# ESP32.net
KiCad netlist of a schematic drawn in Altium Designer
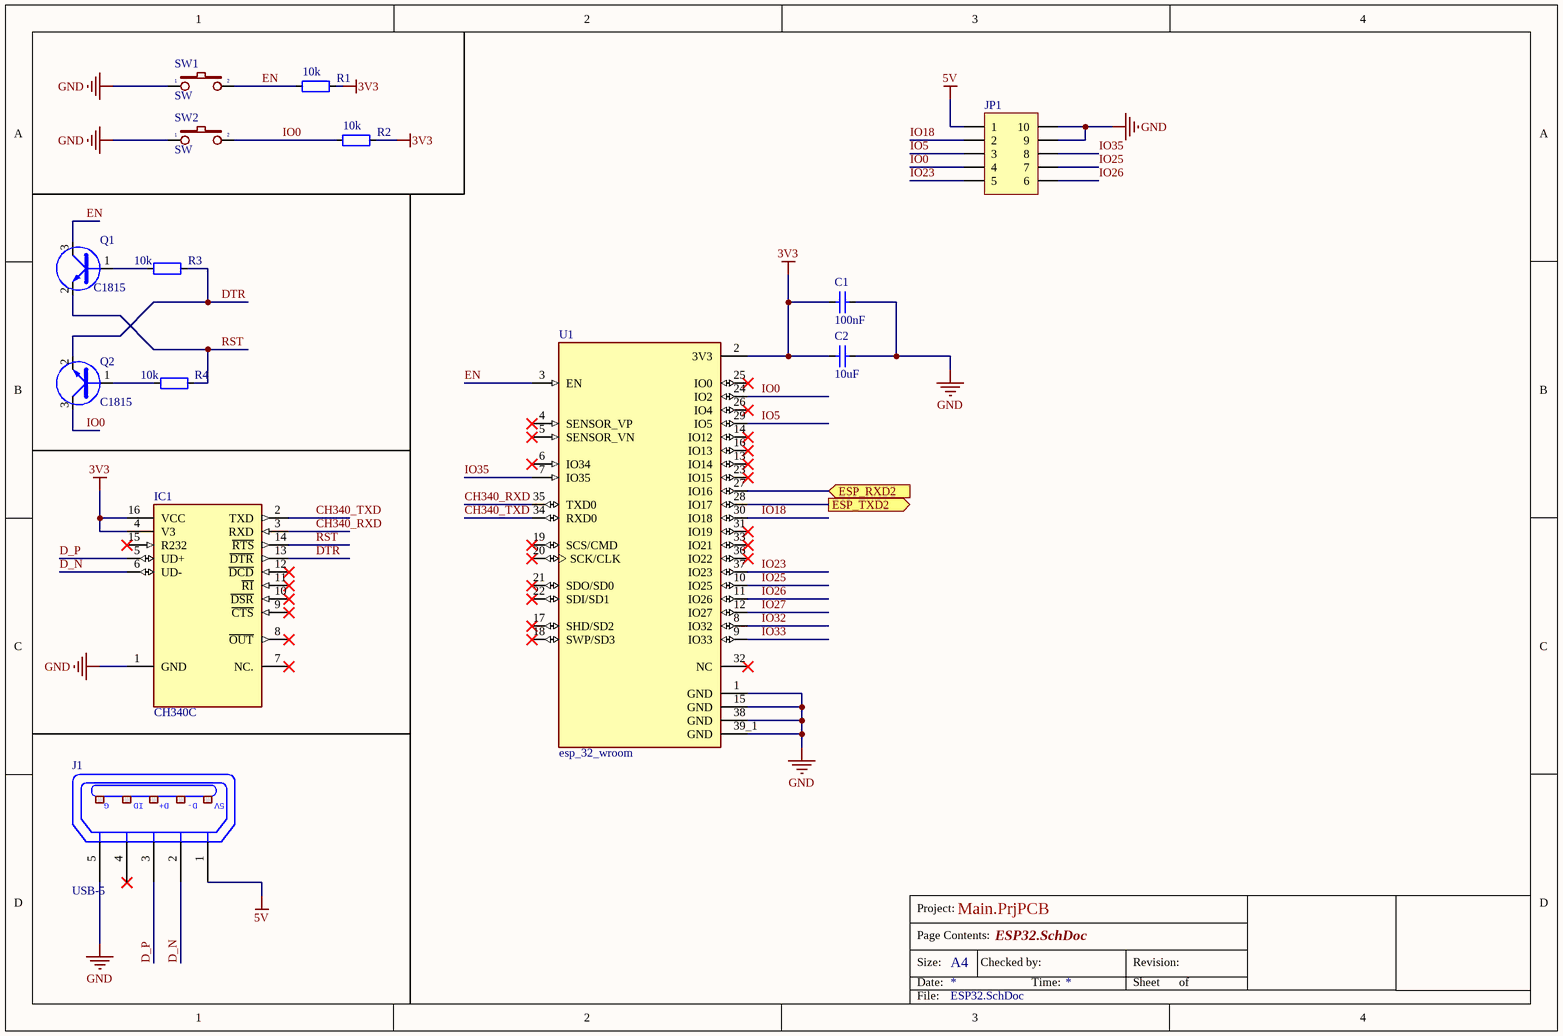
[diagram p0: ESP32.SchDoc]

(export (version "E")
  (design (tool "Eeschema 10.0.6"))
  (components
    (comp (ref "C1")
      (value "100nF")
      (footprint "CAP_0805")
      (description "Capacitor")
      (fields (field (name "PUBLISHER") "Altium Limited"))
      (libsource (lib "My Library") (part "CapSMD"))
    )
    (comp (ref "C2")
      (value "10uF")
      (footprint "CAP_0805")
      (description "Capacitor")
      (fields (field (name "PUBLISHER") "Altium Limited"))
      (libsource (lib "My Library") (part "CapSMD"))
    )
    (comp (ref "IC1") (value "CH340C") (footprint "SO16") (libsource (lib "My Library") (part "CH340C")))
    (comp (ref "J1")
      (value "USB-5")
      (footprint "USB-M1")
      (fields
        (field (name "MANUFACTURER") "FCI")
        (field (name "MANUFACTURER PART NUMBER") "10118193-0001LF")
        (field (name ".CREATOR") "MM")
        (field (name ".CHECKED PCB") "RF")
        (field (name ".CHECKED SCH") "MM")
      )
      (libsource (lib "My Library") (part "USB-5"))
    )
    (comp (ref "JP1")
      (value "JP 2x5 2.54")
      (footprint "JP5-D2T")
      (description "Cắm")
      (libsource (lib "Altium_Lib_by_KhueNguyenCreator") (part "JP 2x5 2.54 Duc Thang"))
    )
    (comp (ref "Q1")
      (value "C1815")
      (footprint "SOT23D")
      (description "NPN 600mW, ECB")
      (libsource (lib "My Library") (part "2SC1815"))
    )
    (comp (ref "Q2")
      (value "C1815")
      (footprint "SOT23D")
      (description "NPN 600mW, ECB")
      (libsource (lib "") (part "2SC1815_1"))
    )
    (comp (ref "R1")
      (value "10k")
      (footprint "RES-SMD-0805")
      (description "Resistor")
      (fields
        (field (name "MANUFACTURER") "Generic Components")
        (field (name "PUBLISHER") "Altium Hobart Technology Centre")
      )
      (libsource (lib "My Library") (part "Resistor - SMD"))
    )
    (comp (ref "R2")
      (value "10k")
      (footprint "RES-SMD-0805")
      (description "Resistor")
      (fields
        (field (name "MANUFACTURER") "Generic Components")
        (field (name "PUBLISHER") "Altium Hobart Technology Centre")
      )
      (libsource (lib "My Library") (part "Resistor - SMD"))
    )
    (comp (ref "R3")
      (value "10k")
      (footprint "RES-SMD-0805")
      (description "Resistor")
      (fields
        (field (name "MANUFACTURER") "Generic Components")
        (field (name "PUBLISHER") "Altium Hobart Technology Centre")
      )
      (libsource (lib "My Library") (part "Resistor - SMD"))
    )
    (comp (ref "R4")
      (value "10k")
      (footprint "RES-SMD-0805")
      (description "Resistor")
      (fields
        (field (name "MANUFACTURER") "Generic Components")
        (field (name "PUBLISHER") "Altium Hobart Technology Centre")
      )
      (libsource (lib "My Library") (part "Resistor - SMD"))
    )
    (comp (ref "SW1")
      (value "SW")
      (footprint "SW2")
      (description "Switch button 2 pin")
      (libsource (lib "My Library") (part "SW2"))
    )
    (comp (ref "SW2")
      (value "SW")
      (footprint "SW2")
      (description "Switch button 2 pin")
      (libsource (lib "My Library") (part "SW2"))
    )
    (comp (ref "U1")
      (value "esp_32_wroom")
      (footprint "MODULE_ESP32-WROOM-32")
      (libsource (lib "My Library") (part "esp_32_wroom"))
    )
  )
  (nets
    (net (code "1") (name "/CH340_RXD") (class "Default")
      (node (ref "IC1") (pin "3") (pinfunction "RXD_3") (pintype "input"))
      (node (ref "U1") (pin "35") (pinfunction "TXD0_35") (pintype "bidirectional"))
    )
    (net (code "2") (name "/CH340_TXD") (class "Default")
      (node (ref "IC1") (pin "2") (pinfunction "TXD_2") (pintype "output"))
      (node (ref "U1") (pin "34") (pinfunction "RXD0_34") (pintype "bidirectional"))
    )
    (net (code "3") (name "/DTR") (class "Default")
      (node (ref "IC1") (pin "13") (pinfunction "~{DTR}_13") (pintype "output"))
      (node (ref "Q2") (pin "2") (pinfunction "E_2") (pintype "passive"))
      (node (ref "R3") (pin "1") (pinfunction "1_1") (pintype "passive"))
    )
    (net (code "4") (name "/D_N") (class "Default")
      (node (ref "IC1") (pin "6") (pinfunction "UD-_6") (pintype "bidirectional"))
      (node (ref "J1") (pin "2") (pinfunction "P2_2") (pintype "passive"))
    )
    (net (code "5") (name "/D_P") (class "Default")
      (node (ref "IC1") (pin "5") (pinfunction "UD+_5") (pintype "bidirectional"))
      (node (ref "J1") (pin "3") (pinfunction "P3_3") (pintype "passive"))
    )
    (net (code "6") (name "/EN") (class "Default")
      (node (ref "Q1") (pin "3") (pinfunction "C_3") (pintype "passive"))
      (node (ref "R1") (pin "2") (pinfunction "2_2") (pintype "passive"))
      (node (ref "SW1") (pin "2") (pinfunction "2_2") (pintype "passive"))
      (node (ref "U1") (pin "3") (pinfunction "EN_3") (pintype "input"))
    )
    (net (code "7") (name "/ESP_RXD2") (class "Default")
      (node (ref "U1") (pin "27") (pinfunction "IO16_27") (pintype "bidirectional"))
    )
    (net (code "8") (name "/ESP_TXD2") (class "Default")
      (node (ref "U1") (pin "28") (pinfunction "IO17_28") (pintype "bidirectional"))
    )
    (net (code "9") (name "/IO0") (class "Default")
      (node (ref "JP1") (pin "4") (pinfunction "4_4") (pintype "passive"))
      (node (ref "Q2") (pin "3") (pinfunction "C_3") (pintype "passive"))
      (node (ref "R2") (pin "2") (pinfunction "2_2") (pintype "passive"))
      (node (ref "SW2") (pin "2") (pinfunction "2_2") (pintype "passive"))
      (node (ref "U1") (pin "24") (pinfunction "IO2_24") (pintype "bidirectional"))
    )
    (net (code "10") (name "/IO5") (class "Default")
      (node (ref "JP1") (pin "3") (pinfunction "3_3") (pintype "passive"))
      (node (ref "U1") (pin "29") (pinfunction "IO5_29") (pintype "bidirectional"))
    )
    (net (code "11") (name "/IO18") (class "Default")
      (node (ref "JP1") (pin "2") (pinfunction "2_2") (pintype "passive"))
      (node (ref "U1") (pin "30") (pinfunction "IO18_30") (pintype "bidirectional"))
    )
    (net (code "12") (name "/IO23") (class "Default")
      (node (ref "JP1") (pin "5") (pinfunction "5_5") (pintype "passive"))
      (node (ref "U1") (pin "37") (pinfunction "IO23_37") (pintype "bidirectional"))
    )
    (net (code "13") (name "/IO25") (class "Default")
      (node (ref "JP1") (pin "7") (pinfunction "7_7") (pintype "passive"))
      (node (ref "U1") (pin "10") (pinfunction "IO25_10") (pintype "bidirectional"))
    )
    (net (code "14") (name "/IO26") (class "Default")
      (node (ref "JP1") (pin "6") (pinfunction "6_6") (pintype "passive"))
      (node (ref "U1") (pin "11") (pinfunction "IO26_11") (pintype "bidirectional"))
    )
    (net (code "15") (name "/IO27") (class "Default")
      (node (ref "U1") (pin "12") (pinfunction "IO27_12") (pintype "bidirectional"))
    )
    (net (code "16") (name "/IO32") (class "Default")
      (node (ref "U1") (pin "8") (pinfunction "IO32_8") (pintype "bidirectional"))
    )
    (net (code "17") (name "/IO33") (class "Default")
      (node (ref "U1") (pin "9") (pinfunction "IO33_9") (pintype "bidirectional"))
    )
    (net (code "18") (name "/IO35") (class "Default")
      (node (ref "JP1") (pin "8") (pinfunction "8_8") (pintype "passive"))
      (node (ref "U1") (pin "7") (pinfunction "IO35_7") (pintype "input"))
    )
    (net (code "19") (name "/RST") (class "Default")
      (node (ref "IC1") (pin "14") (pinfunction "~{RTS}_14") (pintype "output"))
      (node (ref "Q1") (pin "2") (pinfunction "E_2") (pintype "passive"))
      (node (ref "R4") (pin "1") (pinfunction "1_1") (pintype "passive"))
    )
    (net (code "20") (name "3V3") (class "Default")
      (node (ref "C1") (pin "1") (pinfunction "1_1") (pintype "passive"))
      (node (ref "C2") (pin "1") (pinfunction "1_1") (pintype "passive"))
      (node (ref "IC1") (pin "16") (pinfunction "VCC_16") (pintype "power_in"))
      (node (ref "IC1") (pin "4") (pinfunction "V3_4") (pintype "power_in"))
      (node (ref "R1") (pin "1") (pinfunction "1_1") (pintype "passive"))
      (node (ref "R2") (pin "1") (pinfunction "1_1") (pintype "passive"))
      (node (ref "U1") (pin "2") (pinfunction "3V3_2") (pintype "power_in"))
    )
    (net (code "21") (name "5V") (class "Default")
      (node (ref "J1") (pin "1") (pinfunction "P1_1") (pintype "passive"))
      (node (ref "JP1") (pin "1") (pinfunction "1_1") (pintype "passive"))
    )
    (net (code "22") (name "GND") (class "Default")
      (node (ref "C1") (pin "2") (pinfunction "2_2") (pintype "passive"))
      (node (ref "C2") (pin "2") (pinfunction "2_2") (pintype "passive"))
      (node (ref "IC1") (pin "1") (pinfunction "GND_1") (pintype "power_in"))
      (node (ref "J1") (pin "5") (pinfunction "P5_5") (pintype "passive"))
      (node (ref "JP1") (pin "10") (pinfunction "10_10") (pintype "passive"))
      (node (ref "JP1") (pin "9") (pinfunction "9_9") (pintype "passive"))
      (node (ref "SW1") (pin "1") (pinfunction "1_1") (pintype "passive"))
      (node (ref "SW2") (pin "1") (pinfunction "1_1") (pintype "passive"))
      (node (ref "U1") (pin "1") (pinfunction "GND_1") (pintype "power_in"))
      (node (ref "U1") (pin "15") (pinfunction "GND_15") (pintype "power_in"))
      (node (ref "U1") (pin "38") (pinfunction "GND_38") (pintype "power_in"))
      (node (ref "U1") (pin "39_1") (pinfunction "GND_39_1") (pintype "power_in"))
    )
    (net (code "23") (name "Net-(Q1-B)") (class "Default")
      (node (ref "Q1") (pin "1") (pinfunction "B_1") (pintype "passive"))
      (node (ref "R3") (pin "2") (pinfunction "2_2") (pintype "passive"))
    )
    (net (code "24") (name "Net-(Q2-B)") (class "Default")
      (node (ref "Q2") (pin "1") (pinfunction "B_1") (pintype "passive"))
      (node (ref "R4") (pin "2") (pinfunction "2_2") (pintype "passive"))
    )
    (net (code "25") (name "unconnected-(IC1-NC.-Pad7)") (class "Default")
      (node (ref "IC1") (pin "7") (pinfunction "NC._7") (pintype "passive+no_connect"))
    )
    (net (code "26") (name "unconnected-(IC1-R232-Pad15)") (class "Default")
      (node (ref "IC1") (pin "15") (pinfunction "R232_15") (pintype "input+no_connect"))
    )
    (net (code "27") (name "unconnected-(IC1-~{CTS}-Pad9)") (class "Default")
      (node (ref "IC1") (pin "9") (pinfunction "~{CTS}_9") (pintype "input+no_connect"))
    )
    (net (code "28") (name "unconnected-(IC1-~{DCD}-Pad12)") (class "Default")
      (node (ref "IC1") (pin "12") (pinfunction "~{DCD}_12") (pintype "input+no_connect"))
    )
    (net (code "29") (name "unconnected-(IC1-~{DSR}-Pad10)") (class "Default")
      (node (ref "IC1") (pin "10") (pinfunction "~{DSR}_10") (pintype "input+no_connect"))
    )
    (net (code "30") (name "unconnected-(IC1-~{OUT}-Pad8)") (class "Default")
      (node (ref "IC1") (pin "8") (pinfunction "~{OUT}_8") (pintype "output+no_connect"))
    )
    (net (code "31") (name "unconnected-(IC1-~{RI}-Pad11)") (class "Default")
      (node (ref "IC1") (pin "11") (pinfunction "~{RI}_11") (pintype "input+no_connect"))
    )
    (net (code "32") (name "unconnected-(J1-P4-Pad4)") (class "Default")
      (node (ref "J1") (pin "4") (pinfunction "P4_4") (pintype "passive+no_connect"))
    )
    (net (code "33") (name "unconnected-(U1-IO0-Pad25)") (class "Default")
      (node (ref "U1") (pin "25") (pinfunction "IO0_25") (pintype "bidirectional+no_connect"))
    )
    (net (code "34") (name "unconnected-(U1-IO4-Pad26)") (class "Default")
      (node (ref "U1") (pin "26") (pinfunction "IO4_26") (pintype "bidirectional+no_connect"))
    )
    (net (code "35") (name "unconnected-(U1-IO12-Pad14)") (class "Default")
      (node (ref "U1") (pin "14") (pinfunction "IO12_14") (pintype "bidirectional+no_connect"))
    )
    (net (code "36") (name "unconnected-(U1-IO13-Pad16)") (class "Default")
      (node (ref "U1") (pin "16") (pinfunction "IO13_16") (pintype "bidirectional+no_connect"))
    )
    (net (code "37") (name "unconnected-(U1-IO14-Pad13)") (class "Default")
      (node (ref "U1") (pin "13") (pinfunction "IO14_13") (pintype "bidirectional+no_connect"))
    )
    (net (code "38") (name "unconnected-(U1-IO15-Pad23)") (class "Default")
      (node (ref "U1") (pin "23") (pinfunction "IO15_23") (pintype "bidirectional+no_connect"))
    )
    (net (code "39") (name "unconnected-(U1-IO19-Pad31)") (class "Default")
      (node (ref "U1") (pin "31") (pinfunction "IO19_31") (pintype "bidirectional+no_connect"))
    )
    (net (code "40") (name "unconnected-(U1-IO21-Pad33)") (class "Default")
      (node (ref "U1") (pin "33") (pinfunction "IO21_33") (pintype "bidirectional+no_connect"))
    )
    (net (code "41") (name "unconnected-(U1-IO22-Pad36)") (class "Default")
      (node (ref "U1") (pin "36") (pinfunction "IO22_36") (pintype "bidirectional+no_connect"))
    )
    (net (code "42") (name "unconnected-(U1-IO34-Pad6)") (class "Default")
      (node (ref "U1") (pin "6") (pinfunction "IO34_6") (pintype "input+no_connect"))
    )
    (net (code "43") (name "unconnected-(U1-NC-Pad32)") (class "Default")
      (node (ref "U1") (pin "32") (pinfunction "NC_32") (pintype "passive+no_connect"))
    )
    (net (code "44") (name "unconnected-(U1-SCK{slash}CLK-Pad20)") (class "Default")
      (node (ref "U1") (pin "20") (pinfunction "SCK/CLK_20") (pintype "bidirectional+no_connect"))
    )
    (net (code "45") (name "unconnected-(U1-SCS{slash}CMD-Pad19)") (class "Default")
      (node (ref "U1") (pin "19") (pinfunction "SCS/CMD_19") (pintype "bidirectional+no_connect"))
    )
    (net (code "46") (name "unconnected-(U1-SDI{slash}SD1-Pad22)") (class "Default")
      (node (ref "U1") (pin "22") (pinfunction "SDI/SD1_22") (pintype "bidirectional+no_connect"))
    )
    (net (code "47") (name "unconnected-(U1-SDO{slash}SD0-Pad21)") (class "Default")
      (node (ref "U1") (pin "21") (pinfunction "SDO/SD0_21") (pintype "bidirectional+no_connect"))
    )
    (net (code "48") (name "unconnected-(U1-SENSOR_VN-Pad5)") (class "Default")
      (node (ref "U1") (pin "5") (pinfunction "SENSOR_VN_5") (pintype "input+no_connect"))
    )
    (net (code "49") (name "unconnected-(U1-SENSOR_VP-Pad4)") (class "Default")
      (node (ref "U1") (pin "4") (pinfunction "SENSOR_VP_4") (pintype "input+no_connect"))
    )
    (net (code "50") (name "unconnected-(U1-SHD{slash}SD2-Pad17)") (class "Default")
      (node (ref "U1") (pin "17") (pinfunction "SHD/SD2_17") (pintype "bidirectional+no_connect"))
    )
    (net (code "51") (name "unconnected-(U1-SWP{slash}SD3-Pad18)") (class "Default")
      (node (ref "U1") (pin "18") (pinfunction "SWP/SD3_18") (pintype "bidirectional+no_connect"))
    )
  )
)
